# Sheet1.net
KiCad netlist of a schematic drawn in Altium Designer
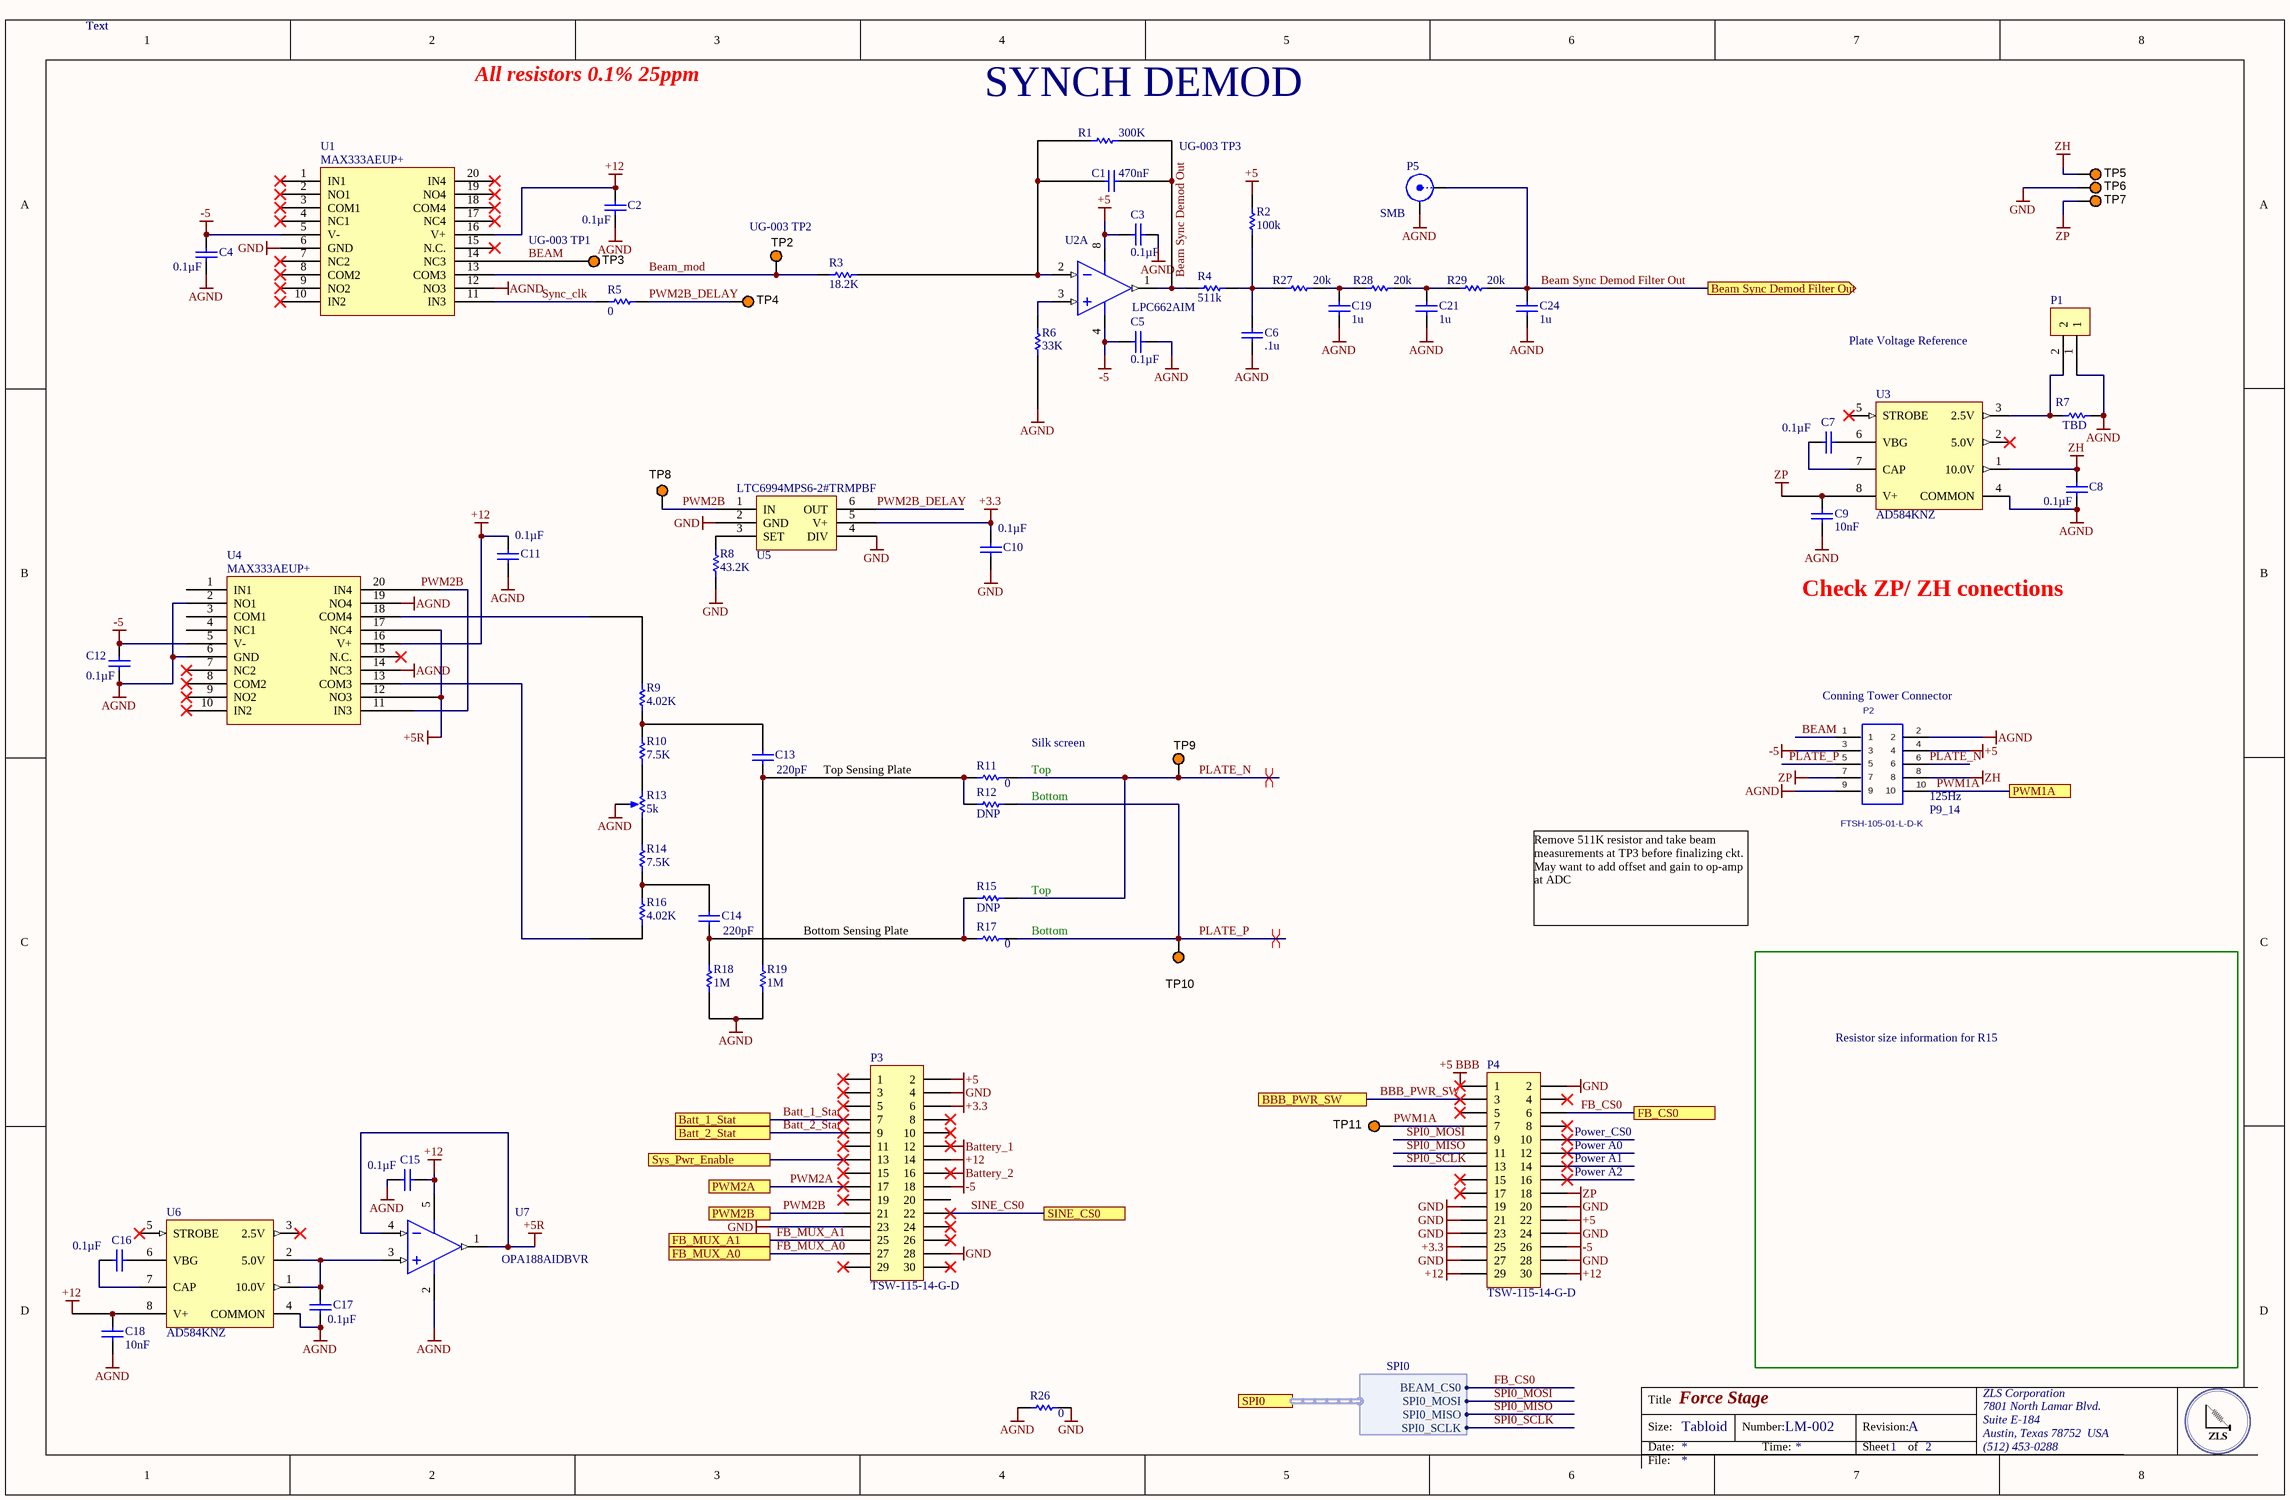
[diagram p0: Sheet1.SchDoc]

(export (version "E")
  (design (tool "Eeschema 10.0.6"))
  (components
    (comp (ref "C1")
      (value "470nF")
      (footprint "CAPC0805(2012)75_L")
      (description "CAP CER 0.47UF 25V X7R 0805")
      (fields
        (field (name "MANUFACTURER") "Murata Electronics North America")
        (field (name "MANUFACTURER PART NUMBER") "GRM219R71E474KA88D")
      )
      (libsource (lib "Altium Content Vault") (part "CMP-1036-02117-1"))
    )
    (comp (ref "C2")
      (value "CAP CER 0.1UF 25V X7R 0805")
      (footprint "CAPC0805(2012)145_N")
      (fields
        (field (name "MANUFACTURER") "Murata Electronics North America")
        (field (name "MANUFACTURER PART NUMBER") "GRM21BR71E104KA01L")
        (field (name "CAPACITANCE") "0.1µF")
        (field (name "TOLERANCE") "±10%")
      )
      (libsource (lib "Altium Content Vault") (part "CMP-1036-04795-1"))
    )
    (comp (ref "C3")
      (value "CAP CER 0.1UF 25V X7R 0805")
      (footprint "CAPC0805(2012)145_N")
      (fields
        (field (name "MANUFACTURER") "Murata Electronics North America")
        (field (name "MANUFACTURER PART NUMBER") "GRM21BR71E104KA01L")
        (field (name "CAPACITANCE") "0.1µF")
        (field (name "TOLERANCE") "±10%")
      )
      (libsource (lib "Altium Content Vault") (part "CMP-1036-04795-1"))
    )
    (comp (ref "C4")
      (value "CAP CER 0.1UF 25V X7R 0805")
      (footprint "CAPC0805(2012)145_N")
      (fields
        (field (name "MANUFACTURER") "Murata Electronics North America")
        (field (name "MANUFACTURER PART NUMBER") "GRM21BR71E104KA01L")
        (field (name "CAPACITANCE") "0.1µF")
        (field (name "TOLERANCE") "±10%")
      )
      (libsource (lib "Altium Content Vault") (part "CMP-1036-04795-1"))
    )
    (comp (ref "C5")
      (value "CAP CER 0.1UF 25V X7R 0805")
      (footprint "CAPC0805(2012)145_N")
      (fields
        (field (name "MANUFACTURER") "Murata Electronics North America")
        (field (name "MANUFACTURER PART NUMBER") "GRM21BR71E104KA01L")
        (field (name "CAPACITANCE") "0.1µF")
        (field (name "TOLERANCE") "±10%")
      )
      (libsource (lib "Altium Content Vault") (part "CMP-1036-04795-1"))
    )
    (comp (ref "C6")
      (value ".1u")
      (footprint "CAPC0805(2012)75_L")
      (description "CAP CER 22UF 25V X5R 0805")
      (libsource (lib "Altium Content Vault") (part "CMP-1036-02117-1"))
    )
    (comp (ref "C7")
      (value "CAP CER 0.1UF 25V X7R 0805")
      (footprint "CAPC0805(2012)145_N")
      (fields
        (field (name "MANUFACTURER") "Murata Electronics North America")
        (field (name "MANUFACTURER PART NUMBER") "GRM21BR71E104KA01L")
        (field (name "CAPACITANCE") "0.1µF")
        (field (name "TOLERANCE") "±10%")
      )
      (libsource (lib "Altium Content Vault") (part "CMP-1036-04795-1"))
    )
    (comp (ref "C8")
      (value "CAP CER 0.1UF 25V X7R 0805")
      (footprint "CAPC0805(2012)145_N")
      (fields
        (field (name "MANUFACTURER") "Murata Electronics North America")
        (field (name "MANUFACTURER PART NUMBER") "GRM21BR71E104KA01L")
        (field (name "CAPACITANCE") "0.1µF")
        (field (name "TOLERANCE") "±10%")
      )
      (libsource (lib "Altium Content Vault") (part "CMP-1036-04795-1"))
    )
    (comp (ref "C9")
      (value "Multilayer Ceramic Capacitors MLCC - SMD/SMT 0.01uF 50volts 10% X7R")
      (footprint "CAPC0805(2012)145_N")
      (fields
        (field (name "MANUFACTURER") "Kemet")
        (field (name "MANUFACTURER PART NUMBER") "C0805C103K5RACAUTO")
        (field (name "CAPACITANCE") "10nF")
        (field (name "TOLERANCE") "10%")
      )
      (libsource (lib "Altium Content Vault") (part "CMP-1036-04795-1"))
    )
    (comp (ref "C10")
      (value "CAP CER 0.1UF 25V X7R 0805")
      (footprint "CAPC0805(2012)145_N")
      (fields
        (field (name "MANUFACTURER") "Murata Electronics North America")
        (field (name "MANUFACTURER PART NUMBER") "GRM21BR71E104KA01L")
        (field (name "CAPACITANCE") "0.1µF")
        (field (name "TOLERANCE") "±10%")
      )
      (libsource (lib "Altium Content Vault") (part "CMP-1036-04795-1"))
    )
    (comp (ref "C11")
      (value "CAP CER 0.1UF 25V X7R 0805")
      (footprint "CAPC0805(2012)145_N")
      (fields
        (field (name "MANUFACTURER") "Murata Electronics North America")
        (field (name "MANUFACTURER PART NUMBER") "GRM21BR71E104KA01L")
        (field (name "CAPACITANCE") "0.1µF")
        (field (name "TOLERANCE") "±10%")
      )
      (libsource (lib "Altium Content Vault") (part "CMP-1036-04795-1"))
    )
    (comp (ref "C12")
      (value "CAP CER 0.1UF 25V X7R 0805")
      (footprint "CAPC0805(2012)145_N")
      (fields
        (field (name "MANUFACTURER") "Murata Electronics North America")
        (field (name "MANUFACTURER PART NUMBER") "GRM21BR71E104KA01L")
        (field (name "CAPACITANCE") "0.1µF")
        (field (name "TOLERANCE") "±10%")
      )
      (libsource (lib "Altium Content Vault") (part "CMP-1036-04795-1"))
    )
    (comp (ref "C13")
      (value "CAP CER 1UF 25V X7R 0805")
      (footprint "CAPC0805(2012)155_L")
      (fields
        (field (name "MANUFACTURER") "Murata Electronics North America")
        (field (name "MANUFACTURER PART NUMBER") "GRM21BR71E105KA99L")
        (field (name "CAPACITANCE") "220pF")
        (field (name "TOLERANCE") "±10%")
      )
      (libsource (lib "Altium Content Vault") (part "CMP-1036-04882-1"))
    )
    (comp (ref "C14")
      (value "CAP CER 1UF 25V X7R 0805")
      (footprint "CAPC0805(2012)155_L")
      (fields
        (field (name "MANUFACTURER") "Murata Electronics North America")
        (field (name "MANUFACTURER PART NUMBER") "GRM21BR71E105KA99L")
        (field (name "CAPACITANCE") "220pF")
        (field (name "TOLERANCE") "±10%")
      )
      (libsource (lib "Altium Content Vault") (part "CMP-1036-04882-1"))
    )
    (comp (ref "C15")
      (value "CAP CER 0.1UF 25V X7R 0805")
      (footprint "CAPC0805(2012)145_N")
      (fields
        (field (name "MANUFACTURER") "Murata Electronics North America")
        (field (name "MANUFACTURER PART NUMBER") "GRM21BR71E104KA01L")
        (field (name "CAPACITANCE") "0.1µF")
        (field (name "TOLERANCE") "±10%")
      )
      (libsource (lib "Altium Content Vault") (part "CMP-1036-04795-1"))
    )
    (comp (ref "C16")
      (value "CAP CER 0.1UF 25V X7R 0805")
      (footprint "CAPC0805(2012)145_N")
      (fields
        (field (name "MANUFACTURER") "Murata Electronics North America")
        (field (name "MANUFACTURER PART NUMBER") "GRM21BR71E104KA01L")
        (field (name "CAPACITANCE") "0.1µF")
        (field (name "TOLERANCE") "±10%")
      )
      (libsource (lib "Altium Content Vault") (part "CMP-1036-04795-1"))
    )
    (comp (ref "C17")
      (value "CAP CER 0.1UF 25V X7R 0805")
      (footprint "CAPC0805(2012)145_N")
      (fields
        (field (name "MANUFACTURER") "Murata Electronics North America")
        (field (name "MANUFACTURER PART NUMBER") "GRM21BR71E104KA01L")
        (field (name "CAPACITANCE") "0.1µF")
        (field (name "TOLERANCE") "±10%")
      )
      (libsource (lib "Altium Content Vault") (part "CMP-1036-04795-1"))
    )
    (comp (ref "C18")
      (value "Multilayer Ceramic Capacitors MLCC - SMD/SMT 0.01uF 50volts 10% X7R")
      (footprint "CAPC0805(2012)145_N")
      (fields
        (field (name "MANUFACTURER") "Kemet")
        (field (name "MANUFACTURER PART NUMBER") "C0805C103K5RACAUTO")
        (field (name "CAPACITANCE") "10nF")
        (field (name "TOLERANCE") "10%")
      )
      (libsource (lib "Altium Content Vault") (part "CMP-1036-04795-1"))
    )
    (comp (ref "C19")
      (value "1u")
      (footprint "CAPC0805(2012)75_L")
      (description "CAP CER 22UF 25V X5R 0805")
      (libsource (lib "Altium Content Vault") (part "CMP-1036-02117-1"))
    )
    (comp (ref "C21")
      (value "1u")
      (footprint "CAPC0805(2012)75_L")
      (description "CAP CER 22UF 25V X5R 0805")
      (libsource (lib "Altium Content Vault") (part "CMP-1036-02117-1"))
    )
    (comp (ref "C24")
      (value "1u")
      (footprint "CAPC0805(2012)75_L")
      (description "CAP CER 22UF 25V X5R 0805")
      (libsource (lib "Altium Content Vault") (part "CMP-1036-02117-1"))
    )
    (comp (ref "P1")
      (value "SSW-102-02-G-S-RA")
      (footprint "SSW-102-02-G-S-RA")
      (description "CONN RCPT .100\" 2POS R/A SGL AU")
      (fields (field (name "MANUFACTURER") "Samtec Inc."))
      (libsource (lib "ZLS_Schematic_lib") (part "SSW-102-02-G-S-RA"))
    )
    (comp (ref "P2")
      (value "FTSH-105-01-L-D-K")
      (footprint "FTSH-105-01-XXX-D-K")
      (description "TERMINAL STRIP, .050\"(1.27mm) PITCH, 10 PINS, KEYING OPTION.")
      (fields (field (name "MANUFACTURER") "Samtec Inc."))
      (libsource (lib "FTSH-105-01-XXX-D-K") (part "FTSH-105-01-XXX-D-K"))
    )
    (comp (ref "P3")
      (value "TSW-115-14-G-D")
      (footprint "TSW-115-14-G-D")
      (description "Header, 15-Pin, Dual row")
      (fields (field (name "MANUFACTURER") "Samtec Inc."))
      (libsource (lib "Miscellaneous Connectors") (part "Header 15X2"))
    )
    (comp (ref "P4")
      (value "TSW-115-14-G-D")
      (footprint "TSW-115-14-G-D")
      (description "Header, 15-Pin, Dual row")
      (fields (field (name "MANUFACTURER") "Samtec Inc."))
      (libsource (lib "Miscellaneous Connectors") (part "Header 15X2"))
    )
    (comp (ref "P5")
      (value "SMB")
      (footprint "RSP-122811-02")
      (description "SMB Straight Connector")
      (fields (field (name "PUBLISHER") "Altium Limited"))
      (libsource (lib "Miscellaneous Connectors") (part "SMB"))
    )
    (comp (ref "R1")
      (value "300K")
      (footprint "RESC0805(2012)_L")
      (description "RES SMD 300K OHM 1% 1/8W 0805")
      (fields
        (field (name "MANUFACTURER") "Vishay Dale")
        (field (name "MANUFACTURER PART NUMBER") "CRCW0805300KFKEAHP")
      )
      (libsource (lib "Altium Content Vault") (part "CMP-1013-00215-1"))
    )
    (comp (ref "R2")
      (value "100k")
      (footprint "RESC0805(2012)_L")
      (description "RES SMD 499K OHM 0.1% 1/8W 0805")
      (fields
        (field (name "MANUFACTURER") "Panasonic Electronic Components")
        (field (name "MANUFACTURER PART NUMBER") "ERA-6AEB4993V")
      )
      (libsource (lib "Altium Content Vault") (part "CMP-1013-00215-1"))
    )
    (comp (ref "R3")
      (value "18.2K")
      (footprint "RESC0805(2012)_L")
      (description "RES SMD 18.2K OHM 1% 1/8W 0805")
      (fields
        (field (name "MANUFACTURER") "Panasonic Electronic Components")
        (field (name "MANUFACTURER PART NUMBER") "ERJ-6ENF1822V")
      )
      (libsource (lib "Altium Content Vault") (part "CMP-1013-00215-1"))
    )
    (comp (ref "R4")
      (value "511k")
      (footprint "RESC0805(2012)_L")
      (description "RES SMD 249K OHM 0.1% 1/8W 0805")
      (fields
        (field (name "MANUFACTURER") "Panasonic Electronic Components")
        (field (name "MANUFACTURER PART NUMBER") "ERA-6AEB2493V")
      )
      (libsource (lib "Altium Content Vault") (part "CMP-1013-00215-1"))
    )
    (comp (ref "R5")
      (value "0")
      (footprint "RESC0805(2012)_L")
      (description "RES SMD 0 OHM JUMPER 1/8W 0805")
      (fields
        (field (name "MANUFACTURER") "Panasonic Electronic Components")
        (field (name "MANUFACTURER PART NUMBER") "ERJ-6GEY0R00V")
      )
      (libsource (lib "Altium Content Vault") (part "CMP-1013-00215-1"))
    )
    (comp (ref "R6")
      (value "33K")
      (footprint "RESC0805(2012)_L")
      (description "RES SMD 33K OHM 1% 1/2W 0805")
      (fields
        (field (name "MANUFACTURER") "Vishay Dale")
        (field (name "MANUFACTURER PART NUMBER") "CRCW080533K0FKEAHP")
      )
      (libsource (lib "Altium Content Vault") (part "CMP-1013-00215-1"))
    )
    (comp (ref "R7")
      (value "TBD")
      (footprint "VH102K")
      (libsource (lib "altium-import") (part "root_0_CMP-1013-00393-1_"))
    )
    (comp (ref "R8")
      (value "43.2K")
      (footprint "RESC0805(2012)_L")
      (description "RES SMD 43.2K OHM 1% 1/8W 0805")
      (fields
        (field (name "MANUFACTURER") "Vishay Dale")
        (field (name "MANUFACTURER PART NUMBER") "CRCW080543K2FKEA")
      )
      (libsource (lib "Altium Content Vault") (part "CMP-1013-00215-1"))
    )
    (comp (ref "R9")
      (value "4.02K")
      (footprint "RESC0805(2012)_L")
      (description "RES SMD 4.02K OHM 1% 1/8W 0805")
      (fields
        (field (name "MANUFACTURER") "Vishay Dale")
        (field (name "MANUFACTURER PART NUMBER") "CRCW08054K02FKEAHP")
      )
      (libsource (lib "Altium Content Vault") (part "CMP-1013-00215-1"))
    )
    (comp (ref "R10")
      (value "7.5K")
      (footprint "RESC0805(2012)_L")
      (description "RES SMD 7.5K OHM 1% 1/8W 0805")
      (fields
        (field (name "MANUFACTURER") "Vishay Dale")
        (field (name "MANUFACTURER PART NUMBER") "CRCW08057K50FKEA")
      )
      (libsource (lib "Altium Content Vault") (part "CMP-1013-00215-1"))
    )
    (comp (ref "R11")
      (value "0")
      (footprint "RESC0805(2012)_L")
      (description "RES SMD 0 OHM JUMPER 1/8W 0805")
      (fields
        (field (name "MANUFACTURER") "Panasonic Electronic Components")
        (field (name "MANUFACTURER PART NUMBER") "ERJ-6GEY0R00V")
      )
      (libsource (lib "Altium Content Vault") (part "CMP-1013-00215-1"))
    )
    (comp (ref "R12")
      (value "DNP")
      (footprint "RESC0805(2012)_L")
      (description "RES SMD 0 OHM JUMPER 1/8W 0805")
      (fields
        (field (name "MANUFACTURER") "Panasonic Electronic Components")
        (field (name "MANUFACTURER PART NUMBER") "ERJ-6GEY0R00V")
      )
      (libsource (lib "Altium Content Vault") (part "CMP-1013-00215-1"))
    )
    (comp (ref "R13")
      (value "TRIMMER 5K OHM 0.25W PC PIN")
      (footprint "Trimmer 2.54")
      (fields
        (field (name "MANUFACTURER") "Vishay Foil Resistors (Division of Vishay Precision Group)")
        (field (name "MANUFACTURER PART NUMBER") "Y00535K00000J0L")
        (field (name "RESISTANCE (OHMS)") "5k")
        (field (name "TOLERANCE") "±5%")
      )
      (libsource (lib "ZLS_Schematic_lib") (part "Trimmer"))
    )
    (comp (ref "R14")
      (value "7.5K")
      (footprint "RESC0805(2012)_L")
      (description "RES SMD 7.5K OHM 1% 1/8W 0805")
      (fields
        (field (name "MANUFACTURER") "Vishay Dale")
        (field (name "MANUFACTURER PART NUMBER") "CRCW08057K50FKEA")
      )
      (libsource (lib "Altium Content Vault") (part "CMP-1013-00215-1"))
    )
    (comp (ref "R15")
      (value "DNP")
      (footprint "RESC0805(2012)_L")
      (description "RES SMD 0 OHM JUMPER 1/8W 0805")
      (fields
        (field (name "MANUFACTURER") "Panasonic Electronic Components")
        (field (name "MANUFACTURER PART NUMBER") "ERJ-6GEY0R00V")
      )
      (libsource (lib "Altium Content Vault") (part "CMP-1013-00215-1"))
    )
    (comp (ref "R16")
      (value "4.02K")
      (footprint "RESC0805(2012)_L")
      (description "RES SMD 4.02K OHM 1% 1/8W 0805")
      (fields
        (field (name "MANUFACTURER") "Vishay Dale")
        (field (name "MANUFACTURER PART NUMBER") "CRCW08054K02FKEAHP")
      )
      (libsource (lib "Altium Content Vault") (part "CMP-1013-00215-1"))
    )
    (comp (ref "R17")
      (value "0")
      (footprint "RESC0805(2012)_L")
      (description "RES SMD 0 OHM JUMPER 1/8W 0805")
      (fields
        (field (name "MANUFACTURER") "Panasonic Electronic Components")
        (field (name "MANUFACTURER PART NUMBER") "ERJ-6GEY0R00V")
      )
      (libsource (lib "Altium Content Vault") (part "CMP-1013-00215-1"))
    )
    (comp (ref "R18")
      (value "1M")
      (footprint "RESC0805(2012)_L")
      (description "RES SMD 1M OHM 1% 1/8W 0805")
      (fields
        (field (name "MANUFACTURER") "Vishay Dale")
        (field (name "MANUFACTURER PART NUMBER") "RCV08051M00FKEA")
      )
      (libsource (lib "Altium Content Vault") (part "CMP-1013-00215-1"))
    )
    (comp (ref "R19")
      (value "1M")
      (footprint "RESC0805(2012)_L")
      (description "RES SMD 1M OHM 1% 1/8W 0805")
      (fields
        (field (name "MANUFACTURER") "Vishay Dale")
        (field (name "MANUFACTURER PART NUMBER") "RCV08051M00FKEA")
      )
      (libsource (lib "Altium Content Vault") (part "CMP-1013-00215-1"))
    )
    (comp (ref "R26")
      (value "0")
      (footprint "RESC0805(2012)_L")
      (description "RES SMD 0 OHM JUMPER 1/8W 0805")
      (fields
        (field (name "MANUFACTURER") "Panasonic Electronic Components")
        (field (name "MANUFACTURER PART NUMBER") "ERJ-6GEY0R00V")
      )
      (libsource (lib "Altium Content Vault") (part "CMP-1013-00215-1"))
    )
    (comp (ref "R27")
      (value "20k")
      (footprint "RESC0805(2012)_L")
      (description "RES SMD 300K OHM 1% 1/8W 0805")
      (fields
        (field (name "MANUFACTURER") "Vishay Dale")
        (field (name "MANUFACTURER PART NUMBER") "CRCW0805300KFKEAHP")
      )
      (libsource (lib "Altium Content Vault") (part "CMP-1013-00215-1"))
    )
    (comp (ref "R28")
      (value "20k")
      (footprint "RESC0805(2012)_L")
      (description "RES SMD 300K OHM 1% 1/8W 0805")
      (fields
        (field (name "MANUFACTURER") "Vishay Dale")
        (field (name "MANUFACTURER PART NUMBER") "CRCW0805300KFKEAHP")
      )
      (libsource (lib "Altium Content Vault") (part "CMP-1013-00215-1"))
    )
    (comp (ref "R29")
      (value "20k")
      (footprint "RESC0805(2012)_L")
      (description "RES SMD 300K OHM 1% 1/8W 0805")
      (fields
        (field (name "MANUFACTURER") "Vishay Dale")
        (field (name "MANUFACTURER PART NUMBER") "CRCW0805300KFKEAHP")
      )
      (libsource (lib "Altium Content Vault") (part "CMP-1013-00215-1"))
    )
    (comp (ref "TP2")
      (value "5003")
      (footprint "KSTN-5003")
      (description "Test Point, Orange, 1-Pin THD, RoHS")
      (libsource (lib "Altium Content Vault") (part "CMP-1672-00009-1"))
    )
    (comp (ref "TP3")
      (value "5003")
      (footprint "KSTN-5003")
      (description "Test Point, Orange, 1-Pin THD, RoHS")
      (libsource (lib "Altium Content Vault") (part "CMP-1672-00009-1"))
    )
    (comp (ref "TP4")
      (value "5003")
      (footprint "KSTN-5003")
      (description "Test Point, Orange, 1-Pin THD, RoHS")
      (libsource (lib "Altium Content Vault") (part "CMP-1672-00009-1"))
    )
    (comp (ref "TP5")
      (value "5003")
      (footprint "KSTN-5003")
      (description "Test Point, Orange, 1-Pin THD, RoHS")
      (libsource (lib "Altium Content Vault") (part "CMP-1672-00009-1"))
    )
    (comp (ref "TP6")
      (value "5003")
      (footprint "KSTN-5003")
      (description "Test Point, Orange, 1-Pin THD, RoHS")
      (libsource (lib "Altium Content Vault") (part "CMP-1672-00009-1"))
    )
    (comp (ref "TP7")
      (value "5003")
      (footprint "KSTN-5003")
      (description "Test Point, Orange, 1-Pin THD, RoHS")
      (libsource (lib "Altium Content Vault") (part "CMP-1672-00009-1"))
    )
    (comp (ref "TP8")
      (value "5003")
      (footprint "KSTN-5003")
      (description "Test Point, Orange, 1-Pin THD, RoHS")
      (libsource (lib "Altium Content Vault") (part "CMP-1672-00009-1"))
    )
    (comp (ref "TP9")
      (value "5003")
      (footprint "KSTN-5003")
      (description "Test Point, Orange, 1-Pin THD, RoHS")
      (libsource (lib "Altium Content Vault") (part "CMP-1672-00009-1"))
    )
    (comp (ref "TP10")
      (value "5003")
      (footprint "KSTN-5003")
      (description "Test Point, Orange, 1-Pin THD, RoHS")
      (libsource (lib "Altium Content Vault") (part "CMP-1672-00009-1"))
    )
    (comp (ref "TP11")
      (value "5003")
      (footprint "KSTN-5003")
      (description "Test Point, Orange, 1-Pin THD, RoHS")
      (libsource (lib "Altium Content Vault") (part "CMP-1672-00009-1"))
    )
    (comp (ref "U1")
      (value "MAX333AEUP+")
      (footprint "TSOP65P640X90-20N")
      (description "IC SWITCH QUAD SPDT 20TSSOP")
      (fields (field (name "MANUFACTURER") "Maxim Integrated") (field (name "BASE PART NUMBER") "MAX333"))
      (libsource (lib "ZLS_Schematic_lib") (part "MAX333CWP+"))
    )
    (comp (ref "U2")
      (value "LPC662AIM")
      (footprint "D0008A_M")
      (description "Low Power CMOS Dual Operational Amplifier, 8-pin Narrow SOIC")
      (fields
        (field (name "MANUFACTURER") "Texas Instruments")
        (field (name "MANUFACTURER PART NUMBER") "LPC662AIM/NOPB")
      )
      (libsource (lib "Altium Content Vault") (part "CMP-0055-00867-3"))
    )
    (comp (ref "U3")
      (value "AD584KNZ")
      (footprint "ADI-N-8")
      (fields
        (field (name "MANUFACTURER") "Analog Devices Inc.")
        (field (name "TOLERANCE") "±0.1%")
        (field (name "BASE PART NUMBER") "AD584")
      )
      (libsource (lib "Altium Content Vault") (part "CMP-0784-00054-1"))
    )
    (comp (ref "U4")
      (value "MAX333AEUP+")
      (footprint "TSOP65P640X90-20N")
      (description "IC SWITCH QUAD SPDT 20TSSOP")
      (fields (field (name "MANUFACTURER") "Maxim Integrated") (field (name "BASE PART NUMBER") "MAX333"))
      (libsource (lib "ZLS_Schematic_lib") (part "MAX333CWP+"))
    )
    (comp (ref "U5")
      (value "LTC6994MPS6-2#TRMPBF")
      (footprint "LTC6994MPS6-2#TRMPBF")
      (description "IC DELAY BLOCK 8TAP PROG TSOT23")
      (fields
        (field (name "MANUFACTURER") "Linear Technology/Analog Devices")
        (field (name "MANUFACTURER PART NUMBER") "LTC6994CS6-2#TRMPBF")
      )
      (libsource (lib "ZLS_Schematic_lib") (part "LTC6994MPS6-2#TRMPBF"))
    )
    (comp (ref "U6")
      (value "AD584KNZ")
      (footprint "ADI-N-8")
      (fields (field (name "MANUFACTURER") "Analog Devices"))
      (libsource (lib "Altium Content Vault") (part "CMP-0784-00054-1"))
    )
    (comp (ref "U7")
      (value "OPA188AIDBVR")
      (footprint "DBV0005A_M")
      (fields (field (name "MANUFACTURER") "Texas Instruments"))
      (libsource (lib "Altium Content Vault") (part "CMP-0809-00005-2"))
    )
  )
  (nets
    (net (code "2") (name "+3.3") (class "Default")
      (node (ref "C10") (pin "1") (pinfunction "1_1") (pintype "passive"))
      (node (ref "P3") (pin "6") (pinfunction "6_6") (pintype "passive"))
      (node (ref "P4") (pin "25") (pinfunction "25_25") (pintype "passive"))
      (node (ref "U5") (pin "5") (pinfunction "V+_5") (pintype "passive"))
    )
    (net (code "3") (name "+5") (class "Default")
      (node (ref "C3") (pin "1") (pinfunction "1_1") (pintype "passive"))
      (node (ref "P2") (pin "4") (pinfunction "4_4") (pintype "passive"))
      (node (ref "P3") (pin "2") (pinfunction "2_2") (pintype "passive"))
      (node (ref "P4") (pin "22") (pinfunction "22_22") (pintype "passive"))
      (node (ref "R2") (pin "2") (pinfunction "2_2") (pintype "passive"))
      (node (ref "U2") (pin "8") (pinfunction "V+_8") (pintype "power_in"))
    )
    (net (code "4") (name "+5 BBB") (class "Default")
      (node (ref "P4") (pin "1") (pinfunction "1_1") (pintype "passive"))
    )
    (net (code "5") (name "+5R") (class "Default")
      (node (ref "U4") (pin "12") (pinfunction "NO3_12") (pintype "passive"))
      (node (ref "U4") (pin "17") (pinfunction "NC4_17") (pintype "passive"))
      (node (ref "U7") (pin "1") (pinfunction "OUT_1") (pintype "output"))
      (node (ref "U7") (pin "4") (pinfunction "IN-_4") (pintype "input"))
    )
    (net (code "6") (name "+12") (class "Default")
      (node (ref "C11") (pin "1") (pinfunction "1_1") (pintype "passive"))
      (node (ref "C15") (pin "2") (pinfunction "2_2") (pintype "passive"))
      (node (ref "C18") (pin "1") (pinfunction "1_1") (pintype "passive"))
      (node (ref "C2") (pin "1") (pinfunction "1_1") (pintype "passive"))
      (node (ref "P3") (pin "14") (pinfunction "14_14") (pintype "passive"))
      (node (ref "P4") (pin "29") (pinfunction "29_29") (pintype "passive"))
      (node (ref "P4") (pin "30") (pinfunction "30_30") (pintype "passive"))
      (node (ref "U1") (pin "16") (pinfunction "V+_16") (pintype "power_in"))
      (node (ref "U4") (pin "16") (pinfunction "V+_16") (pintype "power_in"))
      (node (ref "U6") (pin "8") (pinfunction "V+_8") (pintype "power_in"))
      (node (ref "U7") (pin "5") (pinfunction "V+_5") (pintype "power_in"))
    )
    (net (code "7") (name "-5") (class "Default")
      (node (ref "C12") (pin "1") (pinfunction "1_1") (pintype "passive"))
      (node (ref "C4") (pin "1") (pinfunction "1_1") (pintype "passive"))
      (node (ref "C5") (pin "1") (pinfunction "1_1") (pintype "passive"))
      (node (ref "P2") (pin "3") (pinfunction "3_3") (pintype "passive"))
      (node (ref "P3") (pin "18") (pinfunction "18_18") (pintype "passive"))
      (node (ref "P4") (pin "26") (pinfunction "26_26") (pintype "passive"))
      (node (ref "U1") (pin "5") (pinfunction "V-_5") (pintype "power_in"))
      (node (ref "U2") (pin "4") (pinfunction "V-_4") (pintype "power_in"))
      (node (ref "U4") (pin "5") (pinfunction "V-_5") (pintype "power_in"))
    )
    (net (code "8") (name "/BBB_PWR_SW") (class "Default")
      (node (ref "P4") (pin "3") (pinfunction "3_3") (pintype "passive+no_connect"))
    )
    (net (code "9") (name "/BEAM") (class "Default")
      (node (ref "P2") (pin "1") (pinfunction "1_1") (pintype "passive"))
      (node (ref "TP3") (pin "1") (pinfunction "1_1") (pintype "passive"))
      (node (ref "U1") (pin "14") (pinfunction "NC3_14") (pintype "passive"))
    )
    (net (code "10") (name "/Batt_1_Stat") (class "Default")
      (node (ref "P3") (pin "7") (pinfunction "7_7") (pintype "passive+no_connect"))
    )
    (net (code "11") (name "/Batt_2_Stat") (class "Default")
      (node (ref "P3") (pin "9") (pinfunction "9_9") (pintype "passive+no_connect"))
    )
    (net (code "12") (name "/Beam Sync Demod Filter Out") (class "Default")
      (node (ref "C24") (pin "2") (pinfunction "2_2") (pintype "passive"))
      (node (ref "P5") (pin "1") (pinfunction "X_1") (pintype "passive"))
      (node (ref "R29") (pin "1") (pinfunction "1_1") (pintype "passive"))
    )
    (net (code "13") (name "/Beam Sync Demod Out") (class "Default")
      (node (ref "C1") (pin "2") (pinfunction "2_2") (pintype "passive"))
      (node (ref "R1") (pin "1") (pinfunction "1_1") (pintype "passive"))
      (node (ref "R4") (pin "2") (pinfunction "2_2") (pintype "passive"))
      (node (ref "U2") (pin "1") (pinfunction "OUTA_1") (pintype "output"))
    )
    (net (code "14") (name "/Beam_mod") (class "Default")
      (node (ref "R3") (pin "2") (pinfunction "2_2") (pintype "passive"))
      (node (ref "TP2") (pin "1") (pinfunction "1_1") (pintype "passive"))
      (node (ref "U1") (pin "13") (pinfunction "COM3_13") (pintype "passive"))
    )
    (net (code "15") (name "/FB_CS0") (class "Default")
      (node (ref "P4") (pin "6") (pinfunction "6_6") (pintype "passive"))
    )
    (net (code "16") (name "/FB_MUX_A0") (class "Default")
      (node (ref "P3") (pin "27") (pinfunction "27_27") (pintype "passive"))
    )
    (net (code "17") (name "/FB_MUX_A1") (class "Default")
      (node (ref "P3") (pin "25") (pinfunction "25_25") (pintype "passive"))
    )
    (net (code "18") (name "/PLATE_N") (class "Default")
      (node (ref "P2") (pin "6") (pinfunction "6_6") (pintype "passive"))
      (node (ref "R11") (pin "1") (pinfunction "1_1") (pintype "passive"))
      (node (ref "R15") (pin "1") (pinfunction "1_1") (pintype "passive"))
      (node (ref "TP9") (pin "1") (pinfunction "1_1") (pintype "passive"))
    )
    (net (code "19") (name "/PLATE_P") (class "Default")
      (node (ref "P2") (pin "5") (pinfunction "5_5") (pintype "passive"))
      (node (ref "R12") (pin "1") (pinfunction "1_1") (pintype "passive"))
      (node (ref "R17") (pin "1") (pinfunction "1_1") (pintype "passive"))
      (node (ref "TP10") (pin "1") (pinfunction "1_1") (pintype "passive"))
    )
    (net (code "20") (name "/PWM1A") (class "Default")
      (node (ref "P2") (pin "10") (pinfunction "10_10") (pintype "passive"))
      (node (ref "P4") (pin "7") (pinfunction "7_7") (pintype "passive"))
      (node (ref "TP11") (pin "1") (pinfunction "1_1") (pintype "passive"))
    )
    (net (code "21") (name "/PWM2A") (class "Default")
      (node (ref "P3") (pin "17") (pinfunction "17_17") (pintype "passive+no_connect"))
    )
    (net (code "22") (name "/PWM2B") (class "Default")
      (node (ref "P3") (pin "21") (pinfunction "21_21") (pintype "passive"))
      (node (ref "TP8") (pin "1") (pinfunction "1_1") (pintype "passive"))
      (node (ref "U4") (pin "11") (pinfunction "IN3_11") (pintype "passive"))
      (node (ref "U4") (pin "20") (pinfunction "IN4_20") (pintype "passive"))
      (node (ref "U5") (pin "1") (pinfunction "IN_1") (pintype "passive"))
    )
    (net (code "23") (name "/PWM2B_DELAY") (class "Default")
      (node (ref "R5") (pin "1") (pinfunction "1_1") (pintype "passive"))
      (node (ref "TP4") (pin "1") (pinfunction "1_1") (pintype "passive"))
      (node (ref "U5") (pin "6") (pinfunction "OUT_6") (pintype "passive"))
    )
    (net (code "24") (name "/SINE_CS0") (class "Default")
      (node (ref "P3") (pin "22") (pinfunction "22_22") (pintype "passive+no_connect"))
    )
    (net (code "25") (name "/SPI0_MISO") (class "Default")
      (node (ref "P4") (pin "11") (pinfunction "11_11") (pintype "passive"))
    )
    (net (code "26") (name "/SPI0_MOSI") (class "Default")
      (node (ref "P4") (pin "9") (pinfunction "9_9") (pintype "passive"))
    )
    (net (code "27") (name "/SPI0_SCLK") (class "Default")
      (node (ref "P4") (pin "13") (pinfunction "13_13") (pintype "passive"))
    )
    (net (code "28") (name "/Sync_clk") (class "Default")
      (node (ref "R5") (pin "2") (pinfunction "2_2") (pintype "passive"))
      (node (ref "U1") (pin "11") (pinfunction "IN3_11") (pintype "passive"))
    )
    (net (code "29") (name "/Sys_Pwr_Enable") (class "Default")
      (node (ref "P3") (pin "13") (pinfunction "13_13") (pintype "passive+no_connect"))
    )
    (net (code "31") (name "AGND") (class "Default")
      (node (ref "C11") (pin "2") (pinfunction "2_2") (pintype "passive"))
      (node (ref "C12") (pin "2") (pinfunction "2_2") (pintype "passive"))
      (node (ref "C15") (pin "1") (pinfunction "1_1") (pintype "passive"))
      (node (ref "C17") (pin "2") (pinfunction "2_2") (pintype "passive"))
      (node (ref "C18") (pin "2") (pinfunction "2_2") (pintype "passive"))
      (node (ref "C19") (pin "1") (pinfunction "1_1") (pintype "passive"))
      (node (ref "C2") (pin "2") (pinfunction "2_2") (pintype "passive"))
      (node (ref "C21") (pin "1") (pinfunction "1_1") (pintype "passive"))
      (node (ref "C24") (pin "1") (pinfunction "1_1") (pintype "passive"))
      (node (ref "C3") (pin "2") (pinfunction "2_2") (pintype "passive"))
      (node (ref "C4") (pin "2") (pinfunction "2_2") (pintype "passive"))
      (node (ref "C5") (pin "2") (pinfunction "2_2") (pintype "passive"))
      (node (ref "C6") (pin "1") (pinfunction "1_1") (pintype "passive"))
      (node (ref "C8") (pin "2") (pinfunction "2_2") (pintype "passive"))
      (node (ref "C9") (pin "2") (pinfunction "2_2") (pintype "passive"))
      (node (ref "P1") (pin "1") (pinfunction "1_1") (pintype "passive"))
      (node (ref "P2") (pin "2") (pinfunction "2_2") (pintype "passive"))
      (node (ref "P2") (pin "9") (pinfunction "9_9") (pintype "passive"))
      (node (ref "P5") (pin "2") (pinfunction "Y_2") (pintype "passive"))
      (node (ref "R13") (pin "2") (pinfunction "b_2") (pintype "passive"))
      (node (ref "R18") (pin "1") (pinfunction "1_1") (pintype "passive"))
      (node (ref "R19") (pin "1") (pinfunction "1_1") (pintype "passive"))
      (node (ref "R26") (pin "2") (pinfunction "2_2") (pintype "passive"))
      (node (ref "R6") (pin "1") (pinfunction "1_1") (pintype "passive"))
      (node (ref "R7") (pin "2") (pinfunction "2_2") (pintype "passive"))
      (node (ref "U1") (pin "12") (pinfunction "NO3_12") (pintype "passive"))
      (node (ref "U3") (pin "4") (pinfunction "COMMON_4") (pintype "passive"))
      (node (ref "U4") (pin "14") (pinfunction "NC3_14") (pintype "passive"))
      (node (ref "U4") (pin "19") (pinfunction "NO4_19") (pintype "passive"))
      (node (ref "U4") (pin "2") (pinfunction "NO1_2") (pintype "passive"))
      (node (ref "U4") (pin "6") (pinfunction "GND_6") (pintype "passive"))
      (node (ref "U6") (pin "4") (pinfunction "COMMON_4") (pintype "passive"))
      (node (ref "U7") (pin "2") (pinfunction "V-_2") (pintype "power_in"))
    )
    (net (code "32") (name "Battery_1") (class "Default")
      (node (ref "P3") (pin "12") (pinfunction "12_12") (pintype "passive"))
    )
    (net (code "33") (name "Battery_2") (class "Default")
      (node (ref "P3") (pin "16") (pinfunction "16_16") (pintype "passive"))
    )
    (net (code "34") (name "GND") (class "Default")
      (node (ref "C10") (pin "2") (pinfunction "2_2") (pintype "passive"))
      (node (ref "P3") (pin "23") (pinfunction "23_23") (pintype "passive"))
      (node (ref "P3") (pin "28") (pinfunction "28_28") (pintype "passive"))
      (node (ref "P3") (pin "4") (pinfunction "4_4") (pintype "passive"))
      (node (ref "P4") (pin "19") (pinfunction "19_19") (pintype "passive"))
      (node (ref "P4") (pin "2") (pinfunction "2_2") (pintype "passive"))
      (node (ref "P4") (pin "20") (pinfunction "20_20") (pintype "passive"))
      (node (ref "P4") (pin "21") (pinfunction "21_21") (pintype "passive"))
      (node (ref "P4") (pin "23") (pinfunction "23_23") (pintype "passive"))
      (node (ref "P4") (pin "24") (pinfunction "24_24") (pintype "passive"))
      (node (ref "P4") (pin "27") (pinfunction "27_27") (pintype "passive"))
      (node (ref "P4") (pin "28") (pinfunction "28_28") (pintype "passive"))
      (node (ref "R26") (pin "1") (pinfunction "1_1") (pintype "passive"))
      (node (ref "R8") (pin "2") (pinfunction "2_2") (pintype "passive"))
      (node (ref "TP6") (pin "1") (pinfunction "1_1") (pintype "passive"))
      (node (ref "U1") (pin "6") (pinfunction "GND_6") (pintype "passive"))
      (node (ref "U5") (pin "2") (pinfunction "GND_2") (pintype "passive"))
      (node (ref "U5") (pin "4") (pinfunction "DIV_4") (pintype "passive"))
    )
    (net (code "35") (name "Net-(C6-Pad2)") (class "Default")
      (node (ref "C6") (pin "2") (pinfunction "2_2") (pintype "passive"))
      (node (ref "R2") (pin "1") (pinfunction "1_1") (pintype "passive"))
      (node (ref "R27") (pin "2") (pinfunction "2_2") (pintype "passive"))
      (node (ref "R4") (pin "1") (pinfunction "1_1") (pintype "passive"))
    )
    (net (code "36") (name "Net-(C13-Pad1)") (class "Default")
      (node (ref "C13") (pin "1") (pinfunction "1_1") (pintype "passive"))
      (node (ref "R11") (pin "2") (pinfunction "2_2") (pintype "passive"))
      (node (ref "R12") (pin "2") (pinfunction "2_2") (pintype "passive"))
      (node (ref "R19") (pin "2") (pinfunction "2_2") (pintype "passive"))
    )
    (net (code "37") (name "Net-(C13-Pad2)") (class "Default")
      (node (ref "C13") (pin "2") (pinfunction "2_2") (pintype "passive"))
      (node (ref "R10") (pin "2") (pinfunction "2_2") (pintype "passive"))
      (node (ref "R9") (pin "1") (pinfunction "1_1") (pintype "passive"))
    )
    (net (code "38") (name "Net-(C14-Pad1)") (class "Default")
      (node (ref "C14") (pin "1") (pinfunction "1_1") (pintype "passive"))
      (node (ref "R15") (pin "2") (pinfunction "2_2") (pintype "passive"))
      (node (ref "R17") (pin "2") (pinfunction "2_2") (pintype "passive"))
      (node (ref "R18") (pin "2") (pinfunction "2_2") (pintype "passive"))
    )
    (net (code "39") (name "Net-(C14-Pad2)") (class "Default")
      (node (ref "C14") (pin "2") (pinfunction "2_2") (pintype "passive"))
      (node (ref "R14") (pin "1") (pinfunction "1_1") (pintype "passive"))
      (node (ref "R16") (pin "2") (pinfunction "2_2") (pintype "passive"))
    )
    (net (code "40") (name "Net-(C19-Pad2)") (class "Default")
      (node (ref "C19") (pin "2") (pinfunction "2_2") (pintype "passive"))
      (node (ref "R27") (pin "1") (pinfunction "1_1") (pintype "passive"))
      (node (ref "R28") (pin "2") (pinfunction "2_2") (pintype "passive"))
    )
    (net (code "41") (name "Net-(C21-Pad2)") (class "Default")
      (node (ref "C21") (pin "2") (pinfunction "2_2") (pintype "passive"))
      (node (ref "R28") (pin "1") (pinfunction "1_1") (pintype "passive"))
      (node (ref "R29") (pin "2") (pinfunction "2_2") (pintype "passive"))
    )
    (net (code "42") (name "Net-(R13-a)") (class "Default")
      (node (ref "R10") (pin "1") (pinfunction "1_1") (pintype "passive"))
      (node (ref "R13") (pin "1") (pinfunction "a_1") (pintype "passive"))
    )
    (net (code "43") (name "Net-(R13-c)") (class "Default")
      (node (ref "R13") (pin "3") (pinfunction "c_3") (pintype "passive"))
      (node (ref "R14") (pin "2") (pinfunction "2_2") (pintype "passive"))
    )
    (net (code "44") (name "Net-(U2A-INA+)") (class "Default")
      (node (ref "R6") (pin "2") (pinfunction "2_2") (pintype "passive"))
      (node (ref "U2") (pin "3") (pinfunction "INA+_3") (pintype "input"))
    )
    (net (code "45") (name "Net-(U2A-INA-)") (class "Default")
      (node (ref "C1") (pin "1") (pinfunction "1_1") (pintype "passive"))
      (node (ref "R1") (pin "2") (pinfunction "2_2") (pintype "passive"))
      (node (ref "R3") (pin "1") (pinfunction "1_1") (pintype "passive"))
      (node (ref "U2") (pin "2") (pinfunction "INA-_2") (pintype "input"))
    )
    (net (code "46") (name "Net-(U3-2.5V)") (class "Default")
      (node (ref "P1") (pin "2") (pinfunction "2_2") (pintype "passive"))
      (node (ref "R7") (pin "1") (pinfunction "1_1") (pintype "passive"))
      (node (ref "U3") (pin "3") (pinfunction "2.5V_3") (pintype "output"))
    )
    (net (code "47") (name "Net-(U3-CAP)") (class "Default")
      (node (ref "C7") (pin "1") (pinfunction "1_1") (pintype "passive"))
      (node (ref "U3") (pin "7") (pinfunction "CAP_7") (pintype "passive"))
    )
    (net (code "48") (name "Net-(U3-VBG)") (class "Default")
      (node (ref "C7") (pin "2") (pinfunction "2_2") (pintype "passive"))
      (node (ref "U3") (pin "6") (pinfunction "VBG_6") (pintype "passive"))
    )
    (net (code "49") (name "Net-(U4-COM3)") (class "Default")
      (node (ref "R16") (pin "1") (pinfunction "1_1") (pintype "passive"))
      (node (ref "U4") (pin "13") (pinfunction "COM3_13") (pintype "passive"))
    )
    (net (code "50") (name "Net-(U4-COM4)") (class "Default")
      (node (ref "R9") (pin "2") (pinfunction "2_2") (pintype "passive"))
      (node (ref "U4") (pin "18") (pinfunction "COM4_18") (pintype "passive"))
    )
    (net (code "51") (name "Net-(U5-SET)") (class "Default")
      (node (ref "R8") (pin "1") (pinfunction "1_1") (pintype "passive"))
      (node (ref "U5") (pin "3") (pinfunction "SET_3") (pintype "passive"))
    )
    (net (code "52") (name "Net-(U6-10.0V)") (class "Default")
      (node (ref "C17") (pin "1") (pinfunction "1_1") (pintype "passive"))
      (node (ref "U6") (pin "1") (pinfunction "10.0V_1") (pintype "output"))
      (node (ref "U6") (pin "2") (pinfunction "5.0V_2") (pintype "output"))
      (node (ref "U7") (pin "3") (pinfunction "IN+_3") (pintype "input"))
    )
    (net (code "53") (name "Net-(U6-CAP)") (class "Default")
      (node (ref "C16") (pin "1") (pinfunction "1_1") (pintype "passive"))
      (node (ref "U6") (pin "7") (pinfunction "CAP_7") (pintype "passive"))
    )
    (net (code "54") (name "Net-(U6-VBG)") (class "Default")
      (node (ref "C16") (pin "2") (pinfunction "2_2") (pintype "passive"))
      (node (ref "U6") (pin "6") (pinfunction "VBG_6") (pintype "passive"))
    )
    (net (code "55") (name "ZH") (class "Default")
      (node (ref "C8") (pin "1") (pinfunction "1_1") (pintype "passive"))
      (node (ref "P2") (pin "8") (pinfunction "8_8") (pintype "passive"))
      (node (ref "TP5") (pin "1") (pinfunction "1_1") (pintype "passive"))
      (node (ref "U3") (pin "1") (pinfunction "10.0V_1") (pintype "output"))
    )
    (net (code "56") (name "ZP") (class "Default")
      (node (ref "C9") (pin "1") (pinfunction "1_1") (pintype "passive"))
      (node (ref "P2") (pin "7") (pinfunction "7_7") (pintype "passive"))
      (node (ref "P4") (pin "18") (pinfunction "18_18") (pintype "passive"))
      (node (ref "TP7") (pin "1") (pinfunction "1_1") (pintype "passive"))
      (node (ref "U3") (pin "8") (pinfunction "V+_8") (pintype "power_in"))
    )
    (net (code "57") (name "unconnected-(P3-Pad1)") (class "Default")
      (node (ref "P3") (pin "1") (pinfunction "1_1") (pintype "passive+no_connect"))
    )
    (net (code "58") (name "unconnected-(P3-Pad3)") (class "Default")
      (node (ref "P3") (pin "3") (pinfunction "3_3") (pintype "passive+no_connect"))
    )
    (net (code "59") (name "unconnected-(P3-Pad5)") (class "Default")
      (node (ref "P3") (pin "5") (pinfunction "5_5") (pintype "passive+no_connect"))
    )
    (net (code "60") (name "unconnected-(P3-Pad8)") (class "Default")
      (node (ref "P3") (pin "8") (pinfunction "8_8") (pintype "passive+no_connect"))
    )
    (net (code "61") (name "unconnected-(P3-Pad10)") (class "Default")
      (node (ref "P3") (pin "10") (pinfunction "10_10") (pintype "passive+no_connect"))
    )
    (net (code "62") (name "unconnected-(P3-Pad11)") (class "Default")
      (node (ref "P3") (pin "11") (pinfunction "11_11") (pintype "passive+no_connect"))
    )
    (net (code "63") (name "unconnected-(P3-Pad15)") (class "Default")
      (node (ref "P3") (pin "15") (pinfunction "15_15") (pintype "passive+no_connect"))
    )
    (net (code "64") (name "unconnected-(P3-Pad19)") (class "Default")
      (node (ref "P3") (pin "19") (pinfunction "19_19") (pintype "passive+no_connect"))
    )
    (net (code "65") (name "unconnected-(P3-Pad20)") (class "Default")
      (node (ref "P3") (pin "20") (pinfunction "20_20") (pintype "passive"))
    )
    (net (code "66") (name "unconnected-(P3-Pad24)") (class "Default")
      (node (ref "P3") (pin "24") (pinfunction "24_24") (pintype "passive+no_connect"))
    )
    (net (code "67") (name "unconnected-(P3-Pad26)") (class "Default")
      (node (ref "P3") (pin "26") (pinfunction "26_26") (pintype "passive+no_connect"))
    )
    (net (code "68") (name "unconnected-(P3-Pad29)") (class "Default")
      (node (ref "P3") (pin "29") (pinfunction "29_29") (pintype "passive+no_connect"))
    )
    (net (code "69") (name "unconnected-(P3-Pad30)") (class "Default")
      (node (ref "P3") (pin "30") (pinfunction "30_30") (pintype "passive+no_connect"))
    )
    (net (code "70") (name "unconnected-(P4-Pad4)") (class "Default")
      (node (ref "P4") (pin "4") (pinfunction "4_4") (pintype "passive+no_connect"))
    )
    (net (code "71") (name "unconnected-(P4-Pad5)") (class "Default")
      (node (ref "P4") (pin "5") (pinfunction "5_5") (pintype "passive+no_connect"))
    )
    (net (code "72") (name "unconnected-(P4-Pad8)") (class "Default")
      (node (ref "P4") (pin "8") (pinfunction "8_8") (pintype "passive+no_connect"))
    )
    (net (code "73") (name "unconnected-(P4-Pad10)") (class "Default")
      (node (ref "P4") (pin "10") (pinfunction "10_10") (pintype "passive+no_connect"))
    )
    (net (code "74") (name "unconnected-(P4-Pad12)") (class "Default")
      (node (ref "P4") (pin "12") (pinfunction "12_12") (pintype "passive+no_connect"))
    )
    (net (code "75") (name "unconnected-(P4-Pad14)") (class "Default")
      (node (ref "P4") (pin "14") (pinfunction "14_14") (pintype "passive+no_connect"))
    )
    (net (code "76") (name "unconnected-(P4-Pad15)") (class "Default")
      (node (ref "P4") (pin "15") (pinfunction "15_15") (pintype "passive+no_connect"))
    )
    (net (code "77") (name "unconnected-(P4-Pad16)") (class "Default")
      (node (ref "P4") (pin "16") (pinfunction "16_16") (pintype "passive+no_connect"))
    )
    (net (code "78") (name "unconnected-(P4-Pad17)") (class "Default")
      (node (ref "P4") (pin "17") (pinfunction "17_17") (pintype "passive+no_connect"))
    )
    (net (code "79") (name "unconnected-(U1-COM1-Pad3)") (class "Default")
      (node (ref "U1") (pin "3") (pinfunction "COM1_3") (pintype "passive+no_connect"))
    )
    (net (code "80") (name "unconnected-(U1-COM2-Pad8)") (class "Default")
      (node (ref "U1") (pin "8") (pinfunction "COM2_8") (pintype "passive+no_connect"))
    )
    (net (code "81") (name "unconnected-(U1-COM4-Pad18)") (class "Default")
      (node (ref "U1") (pin "18") (pinfunction "COM4_18") (pintype "passive+no_connect"))
    )
    (net (code "82") (name "unconnected-(U1-IN1-Pad1)") (class "Default")
      (node (ref "U1") (pin "1") (pinfunction "IN1_1") (pintype "passive+no_connect"))
    )
    (net (code "83") (name "unconnected-(U1-IN2-Pad10)") (class "Default")
      (node (ref "U1") (pin "10") (pinfunction "IN2_10") (pintype "passive+no_connect"))
    )
    (net (code "84") (name "unconnected-(U1-IN4-Pad20)") (class "Default")
      (node (ref "U1") (pin "20") (pinfunction "IN4_20") (pintype "passive+no_connect"))
    )
    (net (code "85") (name "unconnected-(U1-N.C.-Pad15)") (class "Default")
      (node (ref "U1") (pin "15") (pinfunction "N.C._15") (pintype "passive+no_connect"))
    )
    (net (code "86") (name "unconnected-(U1-NC1-Pad4)") (class "Default")
      (node (ref "U1") (pin "4") (pinfunction "NC1_4") (pintype "passive+no_connect"))
    )
    (net (code "87") (name "unconnected-(U1-NC2-Pad7)") (class "Default")
      (node (ref "U1") (pin "7") (pinfunction "NC2_7") (pintype "passive+no_connect"))
    )
    (net (code "88") (name "unconnected-(U1-NC4-Pad17)") (class "Default")
      (node (ref "U1") (pin "17") (pinfunction "NC4_17") (pintype "passive+no_connect"))
    )
    (net (code "89") (name "unconnected-(U1-NO1-Pad2)") (class "Default")
      (node (ref "U1") (pin "2") (pinfunction "NO1_2") (pintype "passive+no_connect"))
    )
    (net (code "90") (name "unconnected-(U1-NO2-Pad9)") (class "Default")
      (node (ref "U1") (pin "9") (pinfunction "NO2_9") (pintype "passive+no_connect"))
    )
    (net (code "91") (name "unconnected-(U1-NO4-Pad19)") (class "Default")
      (node (ref "U1") (pin "19") (pinfunction "NO4_19") (pintype "passive+no_connect"))
    )
    (net (code "92") (name "unconnected-(U3-5.0V-Pad2)") (class "Default")
      (node (ref "U3") (pin "2") (pinfunction "5.0V_2") (pintype "output+no_connect"))
    )
    (net (code "93") (name "unconnected-(U3-STROBE-Pad5)") (class "Default")
      (node (ref "U3") (pin "5") (pinfunction "STROBE_5") (pintype "input+no_connect"))
    )
    (net (code "94") (name "unconnected-(U4-COM1-Pad3)") (class "Default")
      (node (ref "U4") (pin "3") (pinfunction "COM1_3") (pintype "passive"))
    )
    (net (code "95") (name "unconnected-(U4-COM2-Pad8)") (class "Default")
      (node (ref "U4") (pin "8") (pinfunction "COM2_8") (pintype "passive+no_connect"))
    )
    (net (code "96") (name "unconnected-(U4-IN1-Pad1)") (class "Default")
      (node (ref "U4") (pin "1") (pinfunction "IN1_1") (pintype "passive"))
    )
    (net (code "97") (name "unconnected-(U4-IN2-Pad10)") (class "Default")
      (node (ref "U4") (pin "10") (pinfunction "IN2_10") (pintype "passive+no_connect"))
    )
    (net (code "98") (name "unconnected-(U4-N.C.-Pad15)") (class "Default")
      (node (ref "U4") (pin "15") (pinfunction "N.C._15") (pintype "passive+no_connect"))
    )
    (net (code "99") (name "unconnected-(U4-NC1-Pad4)") (class "Default")
      (node (ref "U4") (pin "4") (pinfunction "NC1_4") (pintype "passive"))
    )
    (net (code "100") (name "unconnected-(U4-NC2-Pad7)") (class "Default")
      (node (ref "U4") (pin "7") (pinfunction "NC2_7") (pintype "passive+no_connect"))
    )
    (net (code "101") (name "unconnected-(U4-NO2-Pad9)") (class "Default")
      (node (ref "U4") (pin "9") (pinfunction "NO2_9") (pintype "passive+no_connect"))
    )
    (net (code "102") (name "unconnected-(U6-2.5V-Pad3)") (class "Default")
      (node (ref "U6") (pin "3") (pinfunction "2.5V_3") (pintype "output+no_connect"))
    )
    (net (code "103") (name "unconnected-(U6-STROBE-Pad5)") (class "Default")
      (node (ref "U6") (pin "5") (pinfunction "STROBE_5") (pintype "input+no_connect"))
    )
  )
)
